# PLL.net
KiCad netlist of a schematic drawn in EAGLE
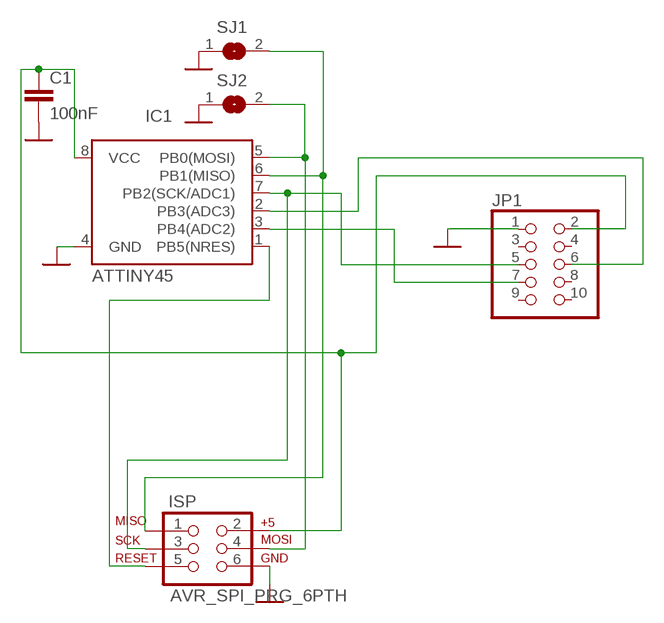
[diagram p0: schematic, sheet 1]

(export (version "E")
  (design (tool "Eeschema 10.0.6"))
  (components
    (comp (ref "C1")
      (value "100nF")
      (footprint "eagle-import:C0805")
      (libsource (lib "eagle-import") (part "C-EUC0805"))
    )
    (comp (ref "IC1")
      (value "ATTINY45")
      (footprint "eagle-import:SO08-EIAJ")
      (libsource (lib "eagle-import") (part "ATTINY45"))
    )
    (comp (ref "ISP")
      (value "AVR_SPI_PRG_6PTH")
      (footprint "eagle-import:2X3")
      (libsource (lib "eagle-import") (part "AVR_SPI_PRG_6PTH"))
    )
    (comp (ref "JP1")
      (value "PINHD-2X5")
      (footprint "eagle-import:2X05")
      (libsource (lib "eagle-import") (part "PINHD-2X5"))
    )
    (comp (ref "SJ1") (value "SJ") (footprint "eagle-import:SJ") (libsource (lib "eagle-import") (part "SJ")))
    (comp (ref "SJ2") (value "SJ") (footprint "eagle-import:SJ") (libsource (lib "eagle-import") (part "SJ")))
  )
  (nets
    (net (code "1") (name "GND") (class "Default")
      (node (ref "C1") (pin "2") (pinfunction "2_2") (pintype "passive"))
      (node (ref "IC1") (pin "4") (pinfunction "GND_4") (pintype "bidirectional"))
      (node (ref "ISP") (pin "6") (pinfunction "6_6") (pintype "passive"))
      (node (ref "JP1") (pin "1") (pinfunction "1_1") (pintype "passive"))
      (node (ref "SJ1") (pin "1") (pinfunction "1_1") (pintype "passive"))
      (node (ref "SJ2") (pin "1") (pinfunction "1_1") (pintype "passive"))
    )
    (net (code "2") (name "Net-(IC1-PB0(MOSI))") (class "Default")
      (node (ref "IC1") (pin "5") (pinfunction "PB0(MOSI)_5") (pintype "bidirectional"))
      (node (ref "ISP") (pin "4") (pinfunction "4_4") (pintype "passive"))
      (node (ref "SJ2") (pin "2") (pinfunction "2_2") (pintype "passive"))
    )
    (net (code "3") (name "Net-(IC1-PB1(MISO))") (class "Default")
      (node (ref "IC1") (pin "6") (pinfunction "PB1(MISO)_6") (pintype "bidirectional"))
      (node (ref "ISP") (pin "1") (pinfunction "1_1") (pintype "passive"))
      (node (ref "SJ1") (pin "2") (pinfunction "2_2") (pintype "passive"))
    )
    (net (code "4") (name "Net-(IC1-PB2(SCK{slash}ADC1))") (class "Default")
      (node (ref "IC1") (pin "7") (pinfunction "PB2(SCK/ADC1)_7") (pintype "bidirectional"))
      (node (ref "ISP") (pin "3") (pinfunction "3_3") (pintype "passive"))
      (node (ref "JP1") (pin "5") (pinfunction "5_5") (pintype "passive"))
    )
    (net (code "5") (name "Net-(IC1-PB3(ADC3))") (class "Default")
      (node (ref "IC1") (pin "2") (pinfunction "PB3(ADC3)_2") (pintype "bidirectional"))
      (node (ref "JP1") (pin "6") (pinfunction "6_6") (pintype "passive"))
    )
    (net (code "6") (name "Net-(IC1-PB4(ADC2))") (class "Default")
      (node (ref "IC1") (pin "3") (pinfunction "PB4(ADC2)_3") (pintype "bidirectional"))
      (node (ref "JP1") (pin "7") (pinfunction "7_7") (pintype "passive"))
    )
    (net (code "7") (name "Net-(IC1-PB5(NRES))") (class "Default")
      (node (ref "IC1") (pin "1") (pinfunction "PB5(NRES)_1") (pintype "bidirectional"))
      (node (ref "ISP") (pin "5") (pinfunction "5_5") (pintype "passive"))
    )
    (net (code "8") (name "Net-(IC1-VCC)") (class "Default")
      (node (ref "C1") (pin "1") (pinfunction "1_1") (pintype "passive"))
      (node (ref "IC1") (pin "8") (pinfunction "VCC_8") (pintype "bidirectional"))
      (node (ref "ISP") (pin "2") (pinfunction "2_2") (pintype "passive"))
      (node (ref "JP1") (pin "2") (pinfunction "2_2") (pintype "passive"))
    )
    (net (code "9") (name "unconnected-(JP1-Pad3)") (class "Default")
      (node (ref "JP1") (pin "3") (pinfunction "3_3") (pintype "passive"))
    )
    (net (code "10") (name "unconnected-(JP1-Pad4)") (class "Default")
      (node (ref "JP1") (pin "4") (pinfunction "4_4") (pintype "passive"))
    )
    (net (code "11") (name "unconnected-(JP1-Pad8)") (class "Default")
      (node (ref "JP1") (pin "8") (pinfunction "8_8") (pintype "passive"))
    )
    (net (code "12") (name "unconnected-(JP1-Pad9)") (class "Default")
      (node (ref "JP1") (pin "9") (pinfunction "9_9") (pintype "passive"))
    )
    (net (code "13") (name "unconnected-(JP1-Pad10)") (class "Default")
      (node (ref "JP1") (pin "10") (pinfunction "10_10") (pintype "passive"))
    )
  )
)
